# RTC.net
KiCad netlist of a schematic drawn in Altium Designer
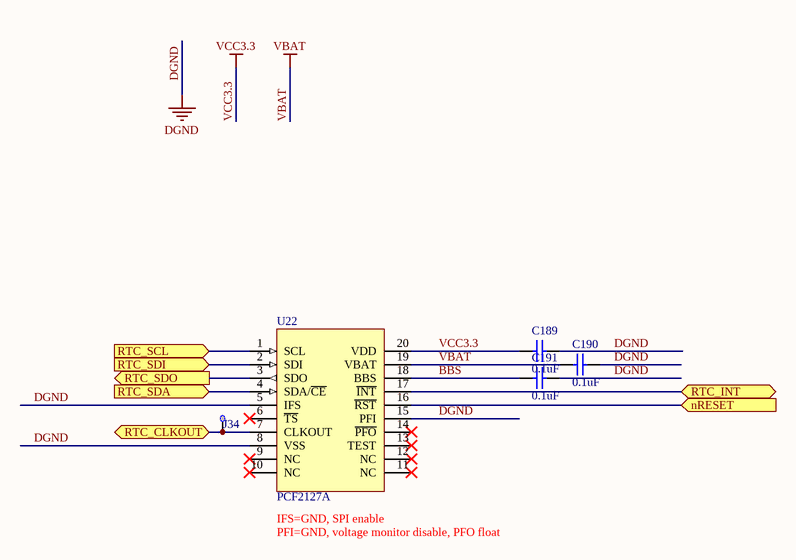
[diagram p0: RTC.SchDoc]

(export (version "E")
  (design (tool "Eeschema 10.0.6"))
  (components
    (comp (ref "C189")
      (value "0.1uF")
      (footprint "0402")
      (description "Capacitor (Semiconductor SIM Model)")
      (fields (field (name "PUBLISHER") "Altium Limited"))
      (libsource (lib "Miscellaneous Devices") (part "Cap Semi"))
    )
    (comp (ref "C190")
      (value "0.1uF")
      (footprint "0402")
      (description "Capacitor (Semiconductor SIM Model)")
      (fields (field (name "PUBLISHER") "Altium Limited"))
      (libsource (lib "Miscellaneous Devices") (part "Cap Semi"))
    )
    (comp (ref "C191")
      (value "0.1uF")
      (footprint "0402")
      (description "Capacitor (Semiconductor SIM Model)")
      (fields (field (name "PUBLISHER") "Altium Limited"))
      (libsource (lib "Miscellaneous Devices") (part "Cap Semi"))
    )
    (comp (ref "J34")
      (value "5004")
      (footprint "TestPoint")
      (description "TEST POINT PC MINI .040\"D YELLOW")
      (libsource (lib "SDR") (part "TestPoint"))
    )
    (comp (ref "U22")
      (value "PCF2127A")
      (footprint "SOIC127P1030X265-20N")
      (description "IC REAL TIME CLK/CALENDAR 20SOIC")
      (libsource (lib "SDR") (part "PCF2127A"))
    )
  )
  (nets
    (net (code "1") (name "/BBS") (class "Default")
      (node (ref "C191") (pin "2") (pinfunction "2_2") (pintype "passive"))
      (node (ref "U22") (pin "18") (pinfunction "BBS_18") (pintype "passive"))
    )
    (net (code "2") (name "/RTC_CLKOUT") (class "Default")
      (node (ref "J34") (pin "1") (pinfunction "TB_1") (pintype "passive"))
      (node (ref "U22") (pin "7") (pinfunction "CLKOUT_7") (pintype "passive"))
    )
    (net (code "3") (name "/RTC_INT") (class "Default")
      (node (ref "U22") (pin "17") (pinfunction "~{INT}_17") (pintype "passive"))
    )
    (net (code "4") (name "/RTC_SCL") (class "Default")
      (node (ref "U22") (pin "1") (pinfunction "SCL_1") (pintype "input"))
    )
    (net (code "5") (name "/RTC_SDA") (class "Default")
      (node (ref "U22") (pin "4") (pinfunction "SDA/~{CE}_4") (pintype "input"))
    )
    (net (code "6") (name "/RTC_SDI") (class "Default")
      (node (ref "U22") (pin "2") (pinfunction "SDI_2") (pintype "input"))
    )
    (net (code "7") (name "/RTC_SDO") (class "Default")
      (node (ref "U22") (pin "3") (pinfunction "SDO_3") (pintype "output"))
    )
    (net (code "8") (name "/nRESET") (class "Default")
      (node (ref "U22") (pin "16") (pinfunction "~{RST}_16") (pintype "passive"))
    )
    (net (code "9") (name "DGND") (class "Default")
      (node (ref "C189") (pin "1") (pinfunction "1_1") (pintype "passive"))
      (node (ref "C190") (pin "1") (pinfunction "1_1") (pintype "passive"))
      (node (ref "C191") (pin "1") (pinfunction "1_1") (pintype "passive"))
      (node (ref "U22") (pin "15") (pinfunction "PFI_15") (pintype "passive"))
      (node (ref "U22") (pin "5") (pinfunction "IFS_5") (pintype "passive"))
      (node (ref "U22") (pin "8") (pinfunction "VSS_8") (pintype "passive"))
    )
    (net (code "10") (name "VBAT") (class "Default")
      (node (ref "C190") (pin "2") (pinfunction "2_2") (pintype "passive"))
      (node (ref "U22") (pin "19") (pinfunction "VBAT_19") (pintype "power_in"))
    )
    (net (code "11") (name "VCC3.3") (class "Default")
      (node (ref "C189") (pin "2") (pinfunction "2_2") (pintype "passive"))
      (node (ref "U22") (pin "20") (pinfunction "VDD_20") (pintype "power_in"))
    )
    (net (code "12") (name "unconnected-(U22-NC-Pad9)") (class "Default")
      (node (ref "U22") (pin "9") (pinfunction "NC_9") (pintype "passive+no_connect"))
    )
    (net (code "13") (name "unconnected-(U22-NC-Pad10)") (class "Default")
      (node (ref "U22") (pin "10") (pinfunction "NC_10") (pintype "passive+no_connect"))
    )
    (net (code "14") (name "unconnected-(U22-NC-Pad11)") (class "Default")
      (node (ref "U22") (pin "11") (pinfunction "NC_11") (pintype "passive+no_connect"))
    )
    (net (code "15") (name "unconnected-(U22-NC-Pad12)") (class "Default")
      (node (ref "U22") (pin "12") (pinfunction "NC_12") (pintype "passive+no_connect"))
    )
    (net (code "16") (name "unconnected-(U22-TEST-Pad13)") (class "Default")
      (node (ref "U22") (pin "13") (pinfunction "TEST_13") (pintype "passive+no_connect"))
    )
    (net (code "17") (name "unconnected-(U22-~{PFO}-Pad14)") (class "Default")
      (node (ref "U22") (pin "14") (pinfunction "~{PFO}_14") (pintype "passive+no_connect"))
    )
    (net (code "18") (name "unconnected-(U22-~{TS}-Pad6)") (class "Default")
      (node (ref "U22") (pin "6") (pinfunction "~{TS}_6") (pintype "passive+no_connect"))
    )
  )
)
